# DAC_Shield_Rev_A.net
KiCad netlist of a schematic drawn in EAGLE
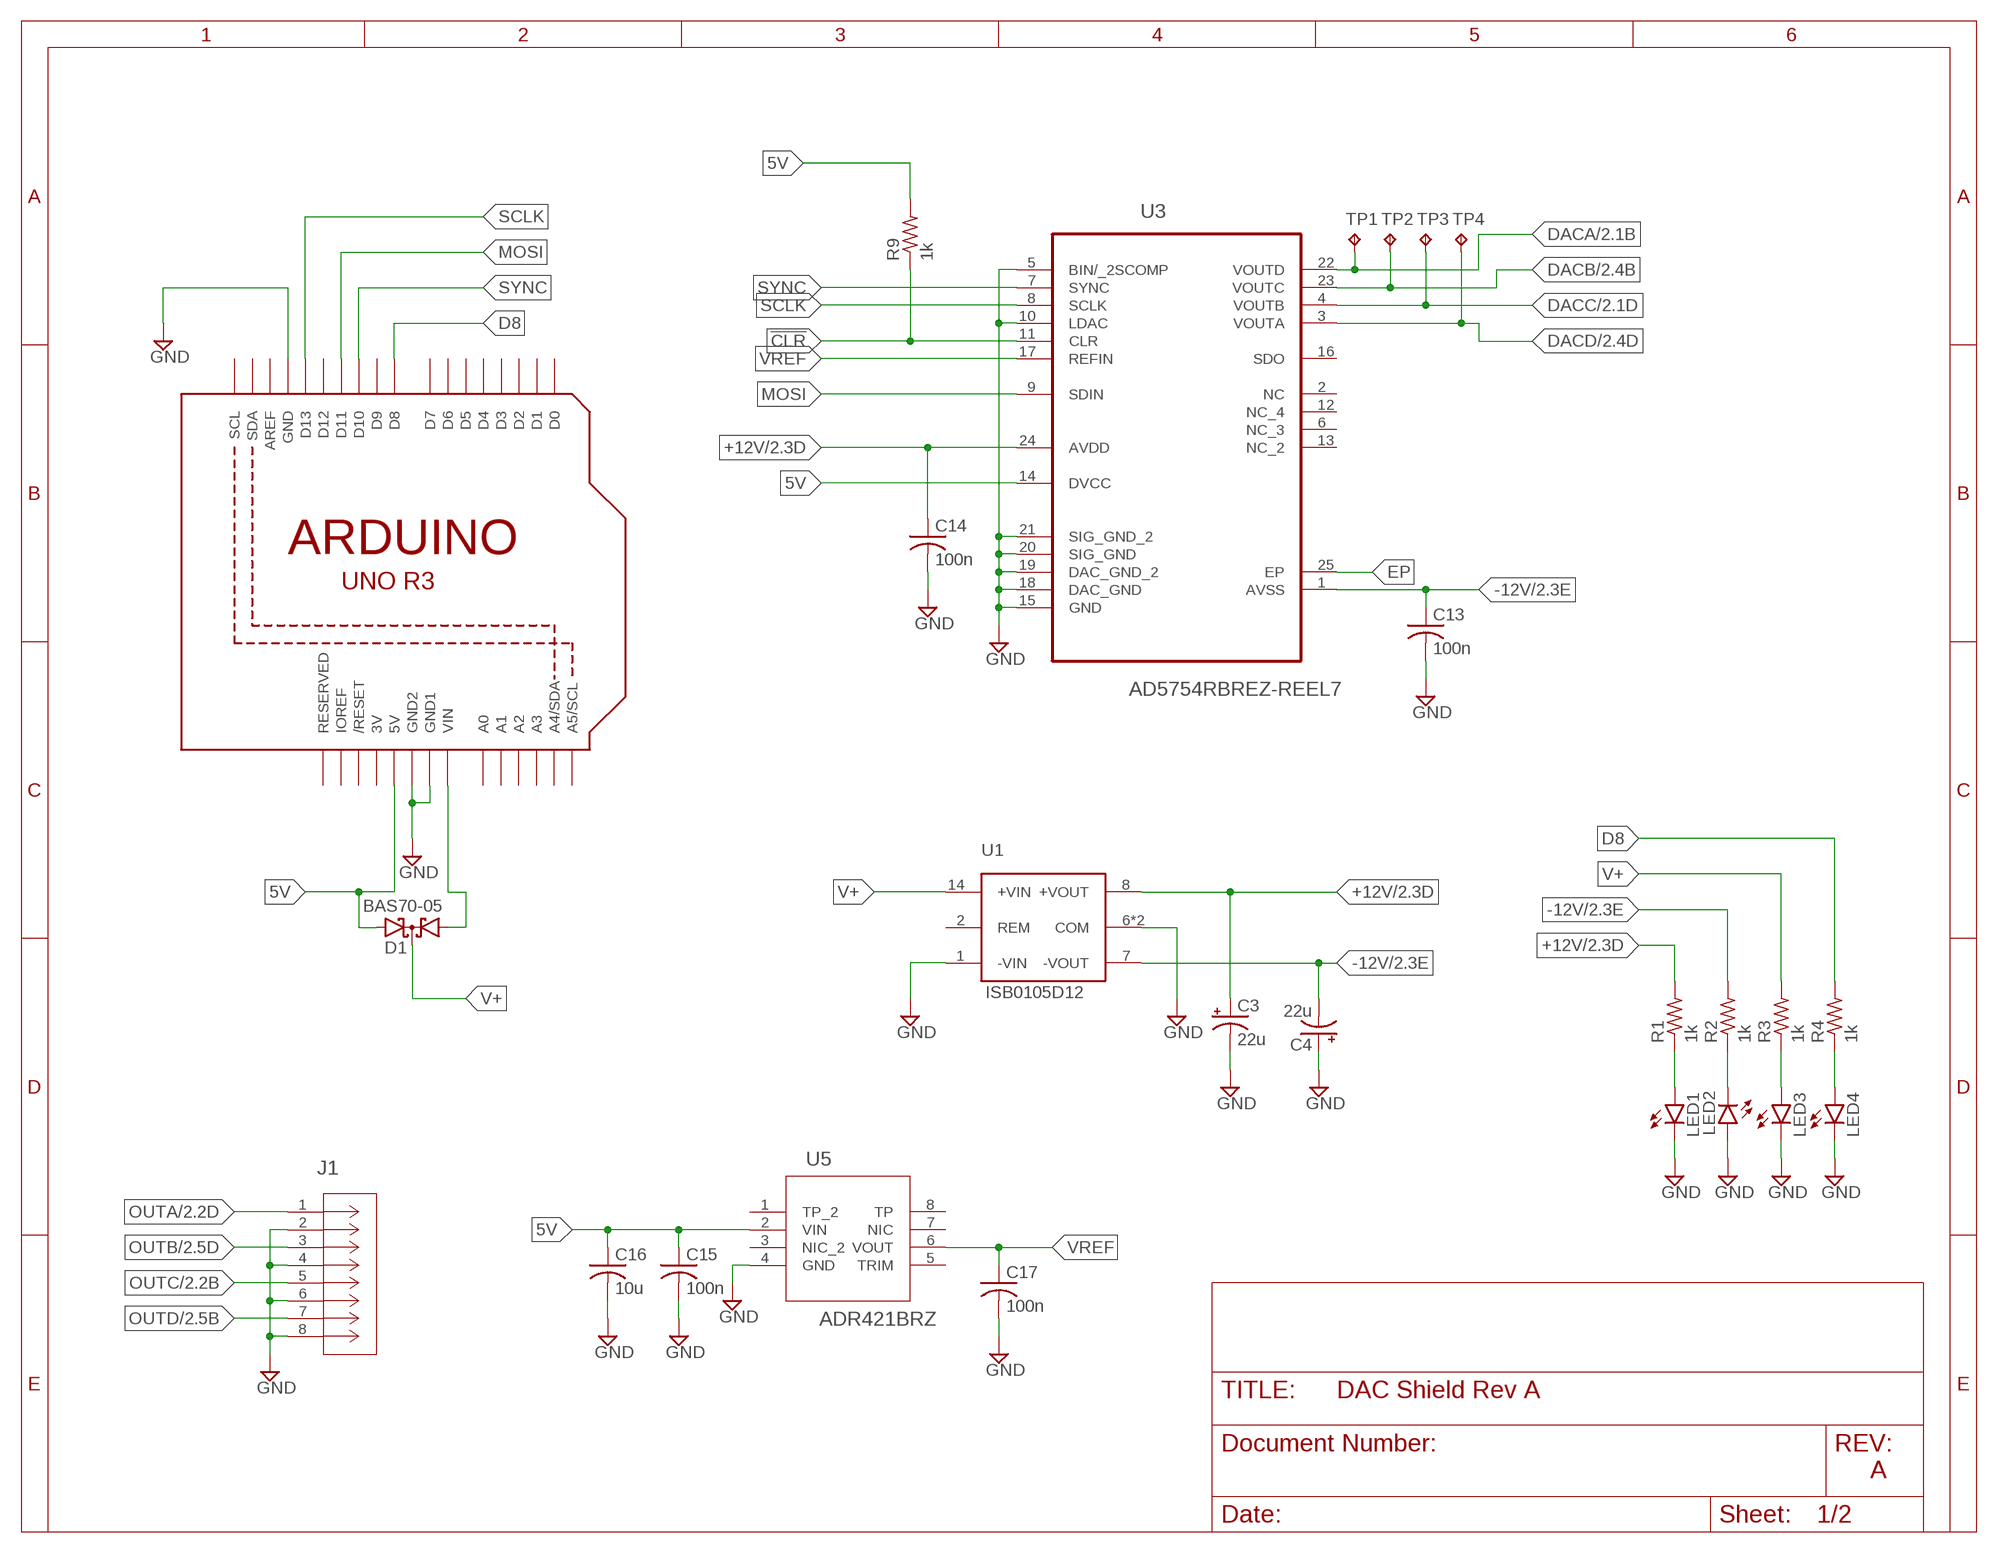
[diagram p0: schematic, sheet 1]
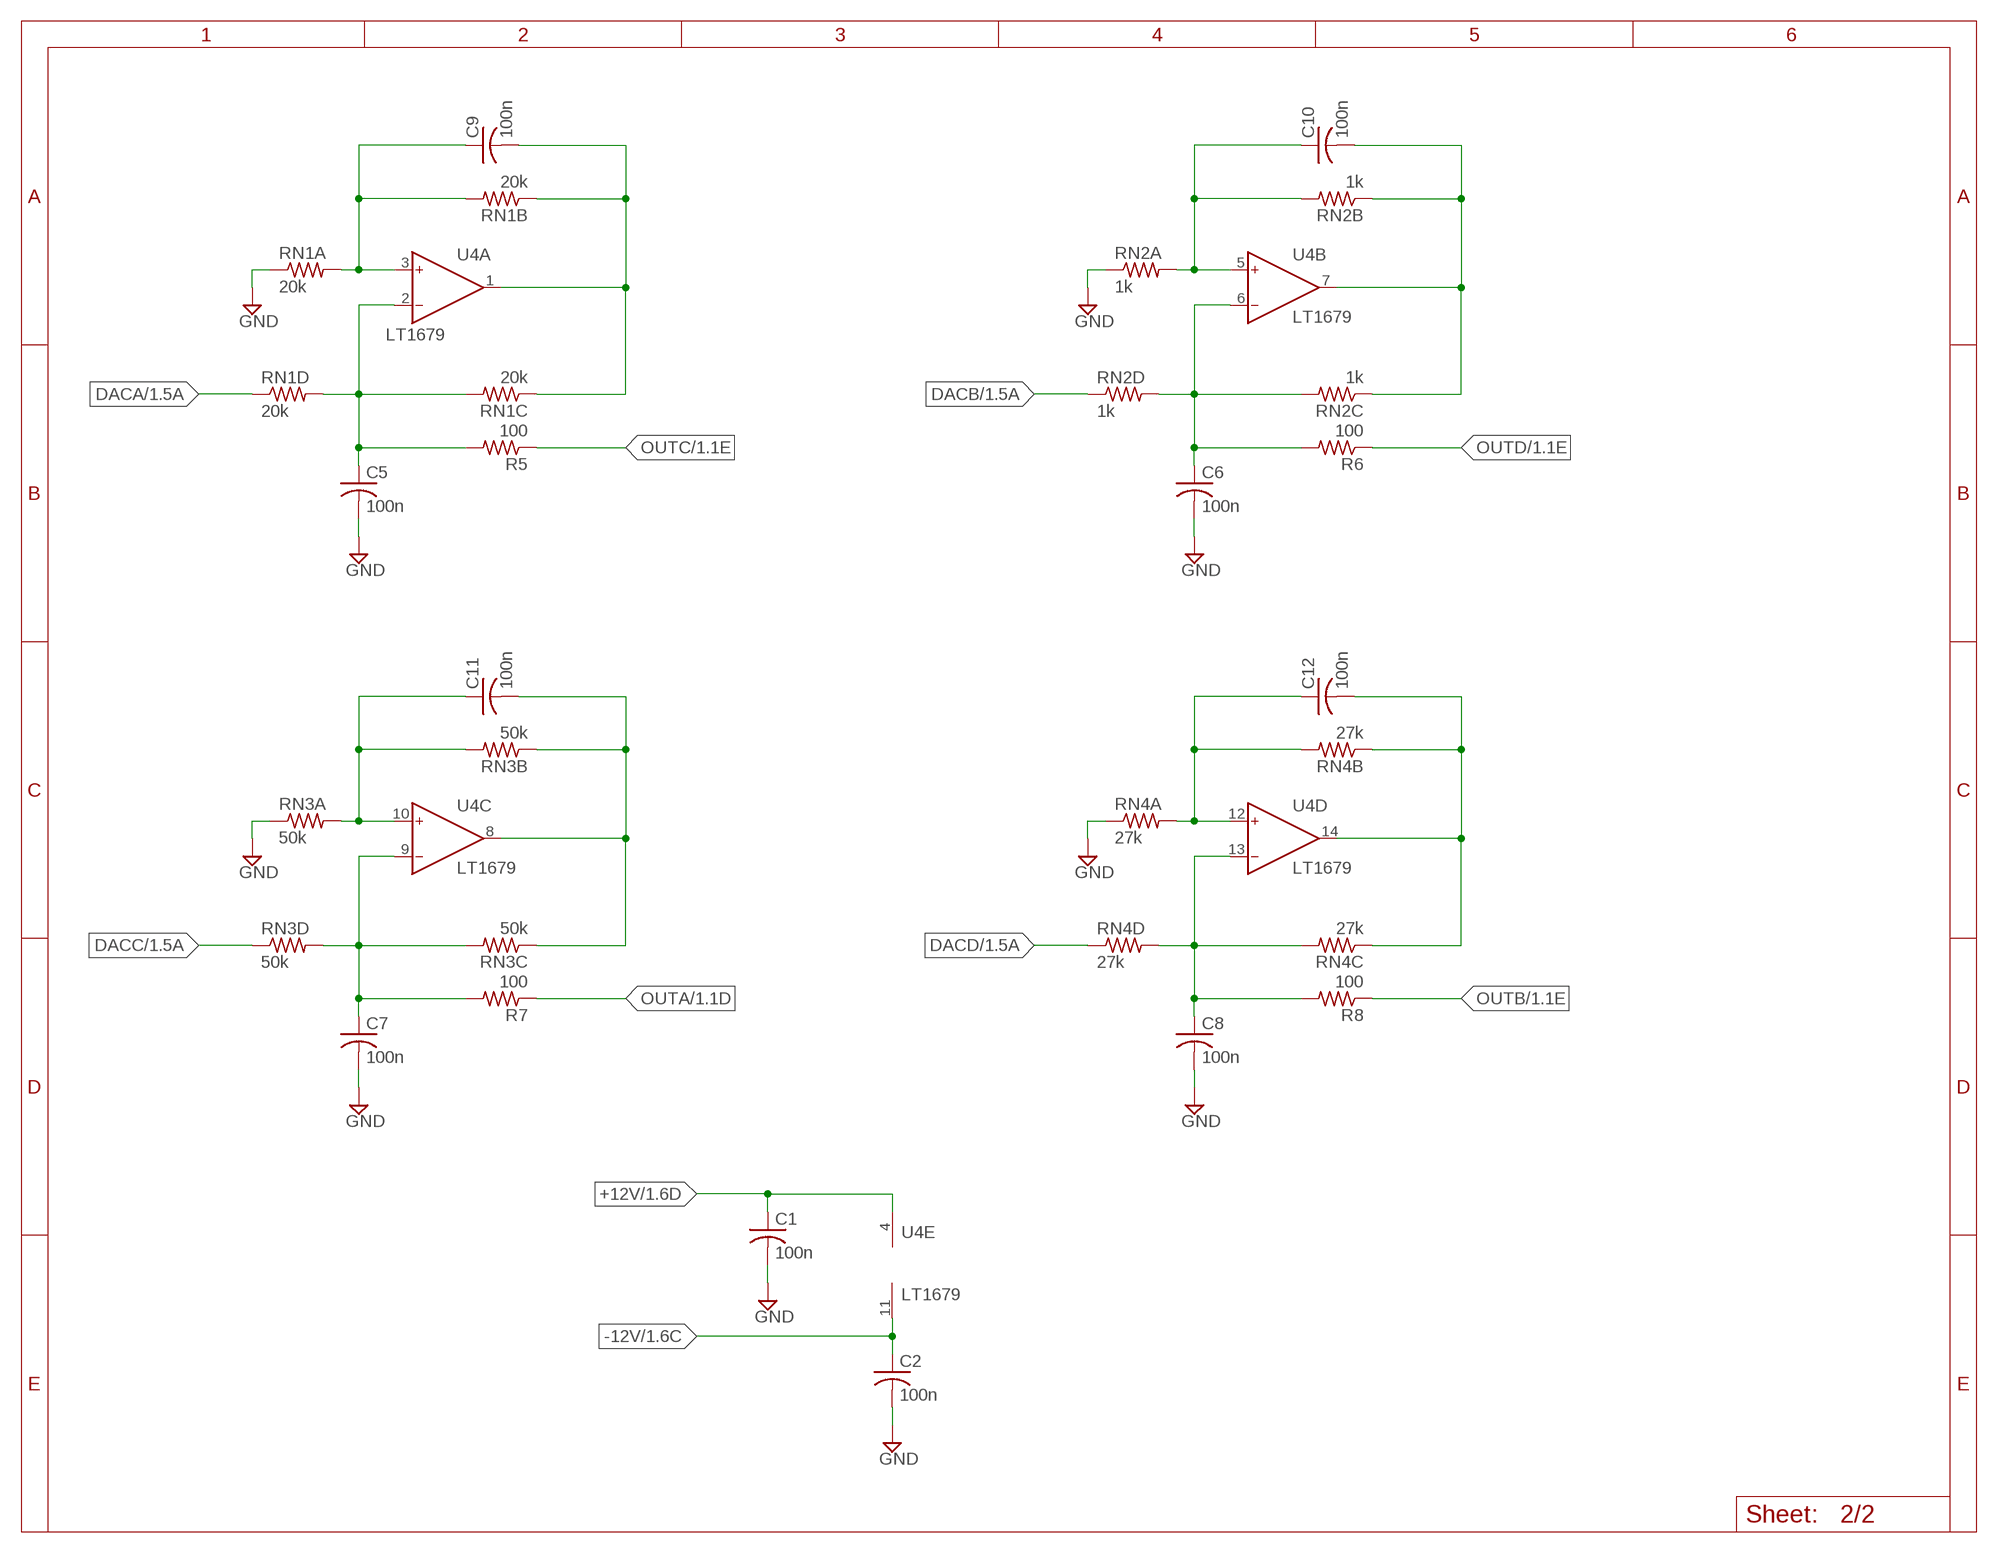
[diagram p1: schematic, sheet 2]

(export (version "E")
  (design (tool "Eeschema 10.0.6"))
  (components
    (comp (ref "C3")
      (value "22u")
      (footprint "eagle-import:C_6032-28W")
      (libsource (lib "eagle-import") (part "CPOL-USC/6032-28W"))
    )
    (comp (ref "C4")
      (value "22u")
      (footprint "eagle-import:C_6032-28W")
      (libsource (lib "eagle-import") (part "CPOL-USC/6032-28W"))
    )
    (comp (ref "C13")
      (value "100n")
      (footprint "eagle-import:C0805")
      (libsource (lib "eagle-import") (part "C-USC0805"))
    )
    (comp (ref "C14")
      (value "100n")
      (footprint "eagle-import:C0805")
      (libsource (lib "eagle-import") (part "C-USC0805"))
    )
    (comp (ref "C15")
      (value "100n")
      (footprint "eagle-import:C0805")
      (libsource (lib "eagle-import") (part "C-USC0805"))
    )
    (comp (ref "C16")
      (value "10u")
      (footprint "eagle-import:C0805")
      (libsource (lib "eagle-import") (part "C-USC0805"))
    )
    (comp (ref "C17")
      (value "100n")
      (footprint "eagle-import:C0805")
      (libsource (lib "eagle-import") (part "C-USC0805"))
    )
    (comp (ref "D1")
      (value "BAS70-05")
      (footprint "eagle-import:SOT23")
      (libsource (lib "eagle-import") (part "BAS70-05"))
    )
    (comp (ref "J1")
      (value "OSTVN08A150")
      (footprint "eagle-import:CONN_OSTVN08A150_OST")
      (fields (field (name "COPYRIGHT") "Copyright (C) 2023 Ultra Librarian. All rights reserved."))
      (libsource (lib "eagle-import") (part "OSTVN08A150"))
    )
    (comp (ref "LED1")
      (value "LEDCHIPLED_0805")
      (footprint "eagle-import:CHIPLED_0805")
      (libsource (lib "eagle-import") (part "LEDCHIPLED_0805"))
    )
    (comp (ref "LED2")
      (value "LEDCHIPLED_0805")
      (footprint "eagle-import:CHIPLED_0805")
      (libsource (lib "eagle-import") (part "LEDCHIPLED_0805"))
    )
    (comp (ref "LED3")
      (value "LEDCHIPLED_0805")
      (footprint "eagle-import:CHIPLED_0805")
      (libsource (lib "eagle-import") (part "LEDCHIPLED_0805"))
    )
    (comp (ref "LED4")
      (value "LEDCHIPLED_0805")
      (footprint "eagle-import:CHIPLED_0805")
      (libsource (lib "eagle-import") (part "LEDCHIPLED_0805"))
    )
    (comp (ref "R1")
      (value "1k")
      (footprint "eagle-import:R0805")
      (libsource (lib "eagle-import") (part "R-US_R0805"))
    )
    (comp (ref "R2")
      (value "1k")
      (footprint "eagle-import:R0805")
      (libsource (lib "eagle-import") (part "R-US_R0805"))
    )
    (comp (ref "R3")
      (value "1k")
      (footprint "eagle-import:R0805")
      (libsource (lib "eagle-import") (part "R-US_R0805"))
    )
    (comp (ref "R4")
      (value "1k")
      (footprint "eagle-import:R0805")
      (libsource (lib "eagle-import") (part "R-US_R0805"))
    )
    (comp (ref "R9")
      (value "1k")
      (footprint "eagle-import:R0805")
      (libsource (lib "eagle-import") (part "R-US_R0805"))
    )
    (comp (ref "TP1")
      (value "TPB1,27")
      (footprint "eagle-import:B1,27")
      (libsource (lib "eagle-import") (part "TPB1,27"))
    )
    (comp (ref "TP2")
      (value "TPB1,27")
      (footprint "eagle-import:B1,27")
      (libsource (lib "eagle-import") (part "TPB1,27"))
    )
    (comp (ref "TP3")
      (value "TPB1,27")
      (footprint "eagle-import:B1,27")
      (libsource (lib "eagle-import") (part "TPB1,27"))
    )
    (comp (ref "TP4")
      (value "TPB1,27")
      (footprint "eagle-import:B1,27")
      (libsource (lib "eagle-import") (part "TPB1,27"))
    )
    (comp (ref "U1")
      (value "ISB0105D12")
      (footprint "eagle-import:SOP254P1860X845-14L")
      (libsource (lib "eagle-import") (part "ISB0105D12ISB0105D12"))
    )
    (comp (ref "U2")
      (value "ARDUINOR3-BPLACE")
      (footprint "eagle-import:ARDUINOR3-BPLACE")
      (libsource (lib "eagle-import") (part "ARDUINOR3-BPLACE"))
    )
    (comp (ref "U3")
      (value "AD5754RBREZ-REEL7")
      (footprint "eagle-import:SOP65P640X120-25N")
      (libsource (lib "eagle-import") (part "AD5754RBREZ-REEL7"))
    )
    (comp (ref "U5")
      (value "ADR421BRZ")
      (footprint "eagle-import:R_8_ADI")
      (fields (field (name "COPYRIGHT") "Copyright (C) 2023 Ultra Librarian. All rights reserved."))
      (libsource (lib "eagle-import") (part "ADR421BRZ"))
    )
    (comp (ref "C1")
      (value "100n")
      (footprint "eagle-import:C0805")
      (libsource (lib "eagle-import") (part "C-USC0805"))
    )
    (comp (ref "C2")
      (value "100n")
      (footprint "eagle-import:C0805")
      (libsource (lib "eagle-import") (part "C-USC0805"))
    )
    (comp (ref "C5")
      (value "100n")
      (footprint "eagle-import:C0805")
      (libsource (lib "eagle-import") (part "C-USC0805"))
    )
    (comp (ref "C6")
      (value "100n")
      (footprint "eagle-import:C0805")
      (libsource (lib "eagle-import") (part "C-USC0805"))
    )
    (comp (ref "C7")
      (value "100n")
      (footprint "eagle-import:C0805")
      (libsource (lib "eagle-import") (part "C-USC0805"))
    )
    (comp (ref "C8")
      (value "100n")
      (footprint "eagle-import:C0805")
      (libsource (lib "eagle-import") (part "C-USC0805"))
    )
    (comp (ref "C9")
      (value "100n")
      (footprint "eagle-import:C0805")
      (libsource (lib "eagle-import") (part "C-USC0805"))
    )
    (comp (ref "C10")
      (value "100n")
      (footprint "eagle-import:C0805")
      (libsource (lib "eagle-import") (part "C-USC0805"))
    )
    (comp (ref "C11")
      (value "100n")
      (footprint "eagle-import:C0805")
      (libsource (lib "eagle-import") (part "C-USC0805"))
    )
    (comp (ref "C12")
      (value "100n")
      (footprint "eagle-import:C0805")
      (libsource (lib "eagle-import") (part "C-USC0805"))
    )
    (comp (ref "R5")
      (value "100")
      (footprint "eagle-import:R0805")
      (libsource (lib "eagle-import") (part "R-US_R0805"))
    )
    (comp (ref "R6")
      (value "100")
      (footprint "eagle-import:R0805")
      (libsource (lib "eagle-import") (part "R-US_R0805"))
    )
    (comp (ref "R7")
      (value "100")
      (footprint "eagle-import:R0805")
      (libsource (lib "eagle-import") (part "R-US_R0805"))
    )
    (comp (ref "R8")
      (value "100")
      (footprint "eagle-import:R0805")
      (libsource (lib "eagle-import") (part "R-US_R0805"))
    )
    (comp (ref "RN1")
      (value "20k")
      (footprint "eagle-import:RESCAV80P320X150X55-8N")
      (libsource (lib "eagle-import") (part "ACASA5001U5001P1ATACASA5001U5001P1AT"))
    )
    (comp (ref "RN2")
      (value "1k")
      (footprint "eagle-import:RESCAV80P320X150X55-8N")
      (libsource (lib "eagle-import") (part "ACASA5001U5001P1ATACASA5001U5001P1AT"))
    )
    (comp (ref "RN3")
      (value "50k")
      (footprint "eagle-import:RESCAV80P320X150X55-8N")
      (libsource (lib "eagle-import") (part "ACASA5001U5001P1ATACASA5001U5001P1AT"))
    )
    (comp (ref "RN4")
      (value "27k")
      (footprint "eagle-import:RESCAV80P320X150X55-8N")
      (libsource (lib "eagle-import") (part "ACASA5001U5001P1ATACASA5001U5001P1AT"))
    )
    (comp (ref "U4")
      (value "LT1679")
      (footprint "eagle-import:R_14_ADI-M")
      (fields
        (field (name "MANUFACTURER_PART_NUMBER") "AD8648ARZ")
        (field (name "COPYRIGHT") "Copyright (C) 2023 Ultra Librarian. All rights reserved.")
      )
      (libsource (lib "eagle-import") (part "AD8648ARZR_14_ADI-M"))
    )
  )
  (nets
    (net (code "1") (name "+12V") (class "Default")
      (node (ref "C1") (pin "1") (pinfunction "1_1") (pintype "passive"))
      (node (ref "C14") (pin "1") (pinfunction "1_1") (pintype "passive"))
      (node (ref "C3") (pin "+") (pinfunction "+_+") (pintype "passive"))
      (node (ref "R1") (pin "2") (pinfunction "2_2") (pintype "passive"))
      (node (ref "U1") (pin "8") (pinfunction "+VOUT_8") (pintype "bidirectional"))
      (node (ref "U3") (pin "24") (pinfunction "AVDD_24") (pintype "power_in"))
      (node (ref "U4") (pin "4") (pinfunction "V+_4") (pintype "power_in"))
    )
    (net (code "2") (name "-12V") (class "Default")
      (node (ref "C13") (pin "1") (pinfunction "1_1") (pintype "passive"))
      (node (ref "C2") (pin "1") (pinfunction "1_1") (pintype "passive"))
      (node (ref "C4") (pin "-") (pinfunction "-_-") (pintype "passive"))
      (node (ref "R2") (pin "2") (pinfunction "2_2") (pintype "passive"))
      (node (ref "U1") (pin "7") (pinfunction "-VOUT_7") (pintype "bidirectional"))
      (node (ref "U3") (pin "1") (pinfunction "AVSS_1") (pintype "passive"))
      (node (ref "U4") (pin "11") (pinfunction "V-_11") (pintype "power_in"))
    )
    (net (code "3") (name "3V") (class "Default")
      (node (ref "U2") (pin "3V") (pinfunction "3V_3V") (pintype "power_in"))
    )
    (net (code "4") (name "5V") (class "Default")
      (node (ref "C15") (pin "1") (pinfunction "1_1") (pintype "passive"))
      (node (ref "C16") (pin "1") (pinfunction "1_1") (pintype "passive"))
      (node (ref "D1") (pin "2") (pinfunction "A2_2") (pintype "passive"))
      (node (ref "R9") (pin "2") (pinfunction "2_2") (pintype "passive"))
      (node (ref "U2") (pin "5V") (pinfunction "5V_5V") (pintype "power_in"))
      (node (ref "U3") (pin "14") (pinfunction "DVCC_14") (pintype "power_in"))
      (node (ref "U5") (pin "2") (pinfunction "VIN_2") (pintype "passive"))
    )
    (net (code "5") (name "D8") (class "Default")
      (node (ref "R4") (pin "2") (pinfunction "2_2") (pintype "passive"))
      (node (ref "U2") (pin "D8") (pinfunction "D8_D8") (pintype "bidirectional"))
    )
    (net (code "6") (name "DACA") (class "Default")
      (node (ref "RN1") (pin "4") (pinfunction "1_4") (pintype "passive"))
      (node (ref "TP1") (pin "TP") (pinfunction "TP_TP") (pintype "input"))
      (node (ref "U3") (pin "22") (pinfunction "VOUTD_22") (pintype "passive"))
    )
    (net (code "7") (name "DACB") (class "Default")
      (node (ref "RN2") (pin "4") (pinfunction "1_4") (pintype "passive"))
      (node (ref "TP2") (pin "TP") (pinfunction "TP_TP") (pintype "input"))
      (node (ref "U3") (pin "23") (pinfunction "VOUTC_23") (pintype "passive"))
    )
    (net (code "8") (name "DACC") (class "Default")
      (node (ref "RN3") (pin "4") (pinfunction "1_4") (pintype "passive"))
      (node (ref "TP3") (pin "TP") (pinfunction "TP_TP") (pintype "input"))
      (node (ref "U3") (pin "4") (pinfunction "VOUTB_4") (pintype "passive"))
    )
    (net (code "9") (name "DACD") (class "Default")
      (node (ref "RN4") (pin "4") (pinfunction "1_4") (pintype "passive"))
      (node (ref "TP4") (pin "TP") (pinfunction "TP_TP") (pintype "input"))
      (node (ref "U3") (pin "3") (pinfunction "VOUTA_3") (pintype "passive"))
    )
    (net (code "10") (name "EP") (class "Default")
      (node (ref "U3") (pin "25") (pinfunction "EP_25") (pintype "power_in"))
    )
    (net (code "11") (name "GND") (class "Default")
      (node (ref "C1") (pin "2") (pinfunction "2_2") (pintype "passive"))
      (node (ref "C13") (pin "2") (pinfunction "2_2") (pintype "passive"))
      (node (ref "C14") (pin "2") (pinfunction "2_2") (pintype "passive"))
      (node (ref "C15") (pin "2") (pinfunction "2_2") (pintype "passive"))
      (node (ref "C16") (pin "2") (pinfunction "2_2") (pintype "passive"))
      (node (ref "C17") (pin "2") (pinfunction "2_2") (pintype "passive"))
      (node (ref "C2") (pin "2") (pinfunction "2_2") (pintype "passive"))
      (node (ref "C3") (pin "-") (pinfunction "-_-") (pintype "passive"))
      (node (ref "C4") (pin "+") (pinfunction "+_+") (pintype "passive"))
      (node (ref "C5") (pin "2") (pinfunction "2_2") (pintype "passive"))
      (node (ref "C6") (pin "2") (pinfunction "2_2") (pintype "passive"))
      (node (ref "C7") (pin "2") (pinfunction "2_2") (pintype "passive"))
      (node (ref "C8") (pin "2") (pinfunction "2_2") (pintype "passive"))
      (node (ref "J1") (pin "2") (pinfunction "2_2") (pintype "passive"))
      (node (ref "J1") (pin "4") (pinfunction "4_4") (pintype "passive"))
      (node (ref "J1") (pin "6") (pinfunction "6_6") (pintype "passive"))
      (node (ref "J1") (pin "8") (pinfunction "8_8") (pintype "passive"))
      (node (ref "LED1") (pin "C") (pinfunction "C_C") (pintype "passive"))
      (node (ref "LED2") (pin "A") (pinfunction "A_A") (pintype "passive"))
      (node (ref "LED3") (pin "C") (pinfunction "C_C") (pintype "passive"))
      (node (ref "LED4") (pin "C") (pinfunction "C_C") (pintype "passive"))
      (node (ref "RN1") (pin "1") (pinfunction "1_1") (pintype "passive"))
      (node (ref "RN2") (pin "1") (pinfunction "1_1") (pintype "passive"))
      (node (ref "RN3") (pin "1") (pinfunction "1_1") (pintype "passive"))
      (node (ref "RN4") (pin "1") (pinfunction "1_1") (pintype "passive"))
      (node (ref "U1") (pin "1") (pinfunction "-VIN_1") (pintype "bidirectional"))
      (node (ref "U1") (pin "6") (pinfunction "COM_6") (pintype "bidirectional"))
      (node (ref "U1") (pin "9") (pinfunction "COM_9") (pintype "bidirectional"))
      (node (ref "U2") (pin "GND") (pinfunction "GND_GND") (pintype "power_in"))
      (node (ref "U2") (pin "GND1") (pinfunction "GND1_GND1") (pintype "power_in"))
      (node (ref "U2") (pin "GND2") (pinfunction "GND2_GND2") (pintype "power_in"))
      (node (ref "U3") (pin "10") (pinfunction "LDAC_10") (pintype "passive"))
      (node (ref "U3") (pin "15") (pinfunction "GND_15") (pintype "passive"))
      (node (ref "U3") (pin "18") (pinfunction "DAC_GND_18") (pintype "passive"))
      (node (ref "U3") (pin "19") (pinfunction "DAC_GND_2_19") (pintype "passive"))
      (node (ref "U3") (pin "20") (pinfunction "SIG_GND_20") (pintype "passive"))
      (node (ref "U3") (pin "21") (pinfunction "SIG_GND_2_21") (pintype "passive"))
      (node (ref "U3") (pin "5") (pinfunction "BIN/_2SCOMP_5") (pintype "passive"))
      (node (ref "U5") (pin "4") (pinfunction "GND_4") (pintype "passive"))
    )
    (net (code "12") (name "MOSI") (class "Default")
      (node (ref "U2") (pin "D11") (pinfunction "D11_D11") (pintype "bidirectional"))
      (node (ref "U3") (pin "9") (pinfunction "SDIN_9") (pintype "passive"))
    )
    (net (code "13") (name "Net-(D1-A1)") (class "Default")
      (node (ref "D1") (pin "1") (pinfunction "A1_1") (pintype "passive"))
      (node (ref "U2") (pin "VIN") (pinfunction "VIN_VIN") (pintype "power_in"))
    )
    (net (code "14") (name "Net-(LED1-PadA)") (class "Default")
      (node (ref "LED1") (pin "A") (pinfunction "A_A") (pintype "passive"))
      (node (ref "R1") (pin "1") (pinfunction "1_1") (pintype "passive"))
    )
    (net (code "15") (name "Net-(LED2-PadC)") (class "Default")
      (node (ref "LED2") (pin "C") (pinfunction "C_C") (pintype "passive"))
      (node (ref "R2") (pin "1") (pinfunction "1_1") (pintype "passive"))
    )
    (net (code "16") (name "Net-(LED3-PadA)") (class "Default")
      (node (ref "LED3") (pin "A") (pinfunction "A_A") (pintype "passive"))
      (node (ref "R3") (pin "1") (pinfunction "1_1") (pintype "passive"))
    )
    (net (code "17") (name "Net-(LED4-PadA)") (class "Default")
      (node (ref "LED4") (pin "A") (pinfunction "A_A") (pintype "passive"))
      (node (ref "R4") (pin "1") (pinfunction "1_1") (pintype "passive"))
    )
    (net (code "18") (name "Net-(RN1A-2)") (class "Default")
      (node (ref "C9") (pin "1") (pinfunction "1_1") (pintype "passive"))
      (node (ref "RN1") (pin "7") (pinfunction "2_7") (pintype "passive"))
      (node (ref "RN1") (pin "8") (pinfunction "2_8") (pintype "passive"))
      (node (ref "U4") (pin "3") (pinfunction "IN+_3") (pintype "input"))
    )
    (net (code "19") (name "Net-(RN1B-1)") (class "Default")
      (node (ref "C9") (pin "2") (pinfunction "2_2") (pintype "passive"))
      (node (ref "RN1") (pin "2") (pinfunction "1_2") (pintype "passive"))
      (node (ref "RN1") (pin "3") (pinfunction "1_3") (pintype "passive"))
      (node (ref "U4") (pin "1") (pinfunction "OUT_1") (pintype "output"))
    )
    (net (code "20") (name "Net-(RN1C-2)") (class "Default")
      (node (ref "C5") (pin "1") (pinfunction "1_1") (pintype "passive"))
      (node (ref "R5") (pin "2") (pinfunction "2_2") (pintype "passive"))
      (node (ref "RN1") (pin "5") (pinfunction "2_5") (pintype "passive"))
      (node (ref "RN1") (pin "6") (pinfunction "2_6") (pintype "passive"))
      (node (ref "U4") (pin "2") (pinfunction "IN-_2") (pintype "input"))
    )
    (net (code "21") (name "Net-(RN2A-2)") (class "Default")
      (node (ref "C10") (pin "1") (pinfunction "1_1") (pintype "passive"))
      (node (ref "RN2") (pin "7") (pinfunction "2_7") (pintype "passive"))
      (node (ref "RN2") (pin "8") (pinfunction "2_8") (pintype "passive"))
      (node (ref "U4") (pin "5") (pinfunction "IN+_5") (pintype "input"))
    )
    (net (code "22") (name "Net-(RN2B-1)") (class "Default")
      (node (ref "C10") (pin "2") (pinfunction "2_2") (pintype "passive"))
      (node (ref "RN2") (pin "2") (pinfunction "1_2") (pintype "passive"))
      (node (ref "RN2") (pin "3") (pinfunction "1_3") (pintype "passive"))
      (node (ref "U4") (pin "7") (pinfunction "OUT_7") (pintype "output"))
    )
    (net (code "23") (name "Net-(RN2C-2)") (class "Default")
      (node (ref "C6") (pin "1") (pinfunction "1_1") (pintype "passive"))
      (node (ref "R6") (pin "2") (pinfunction "2_2") (pintype "passive"))
      (node (ref "RN2") (pin "5") (pinfunction "2_5") (pintype "passive"))
      (node (ref "RN2") (pin "6") (pinfunction "2_6") (pintype "passive"))
      (node (ref "U4") (pin "6") (pinfunction "IN-_6") (pintype "input"))
    )
    (net (code "24") (name "Net-(RN3A-2)") (class "Default")
      (node (ref "C11") (pin "1") (pinfunction "1_1") (pintype "passive"))
      (node (ref "RN3") (pin "7") (pinfunction "2_7") (pintype "passive"))
      (node (ref "RN3") (pin "8") (pinfunction "2_8") (pintype "passive"))
      (node (ref "U4") (pin "10") (pinfunction "IN+_10") (pintype "input"))
    )
    (net (code "25") (name "Net-(RN3B-1)") (class "Default")
      (node (ref "C11") (pin "2") (pinfunction "2_2") (pintype "passive"))
      (node (ref "RN3") (pin "2") (pinfunction "1_2") (pintype "passive"))
      (node (ref "RN3") (pin "3") (pinfunction "1_3") (pintype "passive"))
      (node (ref "U4") (pin "8") (pinfunction "OUT_8") (pintype "output"))
    )
    (net (code "26") (name "Net-(RN3C-2)") (class "Default")
      (node (ref "C7") (pin "1") (pinfunction "1_1") (pintype "passive"))
      (node (ref "R7") (pin "2") (pinfunction "2_2") (pintype "passive"))
      (node (ref "RN3") (pin "5") (pinfunction "2_5") (pintype "passive"))
      (node (ref "RN3") (pin "6") (pinfunction "2_6") (pintype "passive"))
      (node (ref "U4") (pin "9") (pinfunction "IN-_9") (pintype "input"))
    )
    (net (code "27") (name "Net-(RN4A-2)") (class "Default")
      (node (ref "C12") (pin "1") (pinfunction "1_1") (pintype "passive"))
      (node (ref "RN4") (pin "7") (pinfunction "2_7") (pintype "passive"))
      (node (ref "RN4") (pin "8") (pinfunction "2_8") (pintype "passive"))
      (node (ref "U4") (pin "12") (pinfunction "IN+_12") (pintype "input"))
    )
    (net (code "28") (name "Net-(RN4B-1)") (class "Default")
      (node (ref "C12") (pin "2") (pinfunction "2_2") (pintype "passive"))
      (node (ref "RN4") (pin "2") (pinfunction "1_2") (pintype "passive"))
      (node (ref "RN4") (pin "3") (pinfunction "1_3") (pintype "passive"))
      (node (ref "U4") (pin "14") (pinfunction "OUT_14") (pintype "output"))
    )
    (net (code "29") (name "Net-(RN4C-2)") (class "Default")
      (node (ref "C8") (pin "1") (pinfunction "1_1") (pintype "passive"))
      (node (ref "R8") (pin "2") (pinfunction "2_2") (pintype "passive"))
      (node (ref "RN4") (pin "5") (pinfunction "2_5") (pintype "passive"))
      (node (ref "RN4") (pin "6") (pinfunction "2_6") (pintype "passive"))
      (node (ref "U4") (pin "13") (pinfunction "IN-_13") (pintype "input"))
    )
    (net (code "30") (name "OUTA") (class "Default")
      (node (ref "J1") (pin "1") (pinfunction "1_1") (pintype "passive"))
      (node (ref "R7") (pin "1") (pinfunction "1_1") (pintype "passive"))
    )
    (net (code "31") (name "OUTB") (class "Default")
      (node (ref "J1") (pin "3") (pinfunction "3_3") (pintype "passive"))
      (node (ref "R8") (pin "1") (pinfunction "1_1") (pintype "passive"))
    )
    (net (code "32") (name "OUTC") (class "Default")
      (node (ref "J1") (pin "5") (pinfunction "5_5") (pintype "passive"))
      (node (ref "R5") (pin "1") (pinfunction "1_1") (pintype "passive"))
    )
    (net (code "33") (name "OUTD") (class "Default")
      (node (ref "J1") (pin "7") (pinfunction "7_7") (pintype "passive"))
      (node (ref "R6") (pin "1") (pinfunction "1_1") (pintype "passive"))
    )
    (net (code "34") (name "SCLK") (class "Default")
      (node (ref "U2") (pin "D13") (pinfunction "D13_D13") (pintype "bidirectional"))
      (node (ref "U3") (pin "8") (pinfunction "SCLK_8") (pintype "passive"))
    )
    (net (code "35") (name "SYNC") (class "Default")
      (node (ref "U2") (pin "D10") (pinfunction "D10_D10") (pintype "bidirectional"))
      (node (ref "U3") (pin "7") (pinfunction "SYNC_7") (pintype "passive"))
    )
    (net (code "36") (name "V+") (class "Default")
      (node (ref "D1") (pin "3") (pinfunction "C_3") (pintype "passive"))
      (node (ref "R3") (pin "2") (pinfunction "2_2") (pintype "passive"))
      (node (ref "U1") (pin "14") (pinfunction "+VIN_14") (pintype "bidirectional"))
    )
    (net (code "37") (name "VREF") (class "Default")
      (node (ref "C17") (pin "1") (pinfunction "1_1") (pintype "passive"))
      (node (ref "U3") (pin "17") (pinfunction "REFIN_17") (pintype "passive"))
      (node (ref "U5") (pin "6") (pinfunction "VOUT_6") (pintype "passive"))
    )
    (net (code "38") (name "unconnected-(U1-REM-Pad2)") (class "Default")
      (node (ref "U1") (pin "2") (pinfunction "REM_2") (pintype "bidirectional"))
    )
    (net (code "39") (name "unconnected-(U2-A4{slash}SDA-PadA4)") (class "Default")
      (node (ref "U2") (pin "A4") (pinfunction "A4/SDA_A4") (pintype "bidirectional"))
    )
    (net (code "40") (name "unconnected-(U2-A5{slash}SCL-PadA5)") (class "Default")
      (node (ref "U2") (pin "A5") (pinfunction "A5/SCL_A5") (pintype "bidirectional"))
    )
    (net (code "41") (name "unconnected-(U2-PadA0)") (class "Default")
      (node (ref "U2") (pin "A0") (pinfunction "A0_A0") (pintype "bidirectional"))
    )
    (net (code "42") (name "unconnected-(U2-PadA1)") (class "Default")
      (node (ref "U2") (pin "A1") (pinfunction "A1_A1") (pintype "bidirectional"))
    )
    (net (code "43") (name "unconnected-(U2-PadA2)") (class "Default")
      (node (ref "U2") (pin "A2") (pinfunction "A2_A2") (pintype "bidirectional"))
    )
    (net (code "44") (name "unconnected-(U2-PadA3)") (class "Default")
      (node (ref "U2") (pin "A3") (pinfunction "A3_A3") (pintype "bidirectional"))
    )
    (net (code "45") (name "unconnected-(U2-PadAREF)") (class "Default")
      (node (ref "U2") (pin "AREF") (pinfunction "AREF_AREF") (pintype "bidirectional"))
    )
    (net (code "46") (name "unconnected-(U2-PadD0)") (class "Default")
      (node (ref "U2") (pin "D0") (pinfunction "D0_D0") (pintype "bidirectional"))
    )
    (net (code "47") (name "unconnected-(U2-PadD1)") (class "Default")
      (node (ref "U2") (pin "D1") (pinfunction "D1_D1") (pintype "bidirectional"))
    )
    (net (code "48") (name "unconnected-(U2-PadD2)") (class "Default")
      (node (ref "U2") (pin "D2") (pinfunction "D2_D2") (pintype "bidirectional"))
    )
    (net (code "49") (name "unconnected-(U2-PadD3)") (class "Default")
      (node (ref "U2") (pin "D3") (pinfunction "D3_D3") (pintype "bidirectional"))
    )
    (net (code "50") (name "unconnected-(U2-PadD4)") (class "Default")
      (node (ref "U2") (pin "D4") (pinfunction "D4_D4") (pintype "bidirectional"))
    )
    (net (code "51") (name "unconnected-(U2-PadD5)") (class "Default")
      (node (ref "U2") (pin "D5") (pinfunction "D5_D5") (pintype "bidirectional"))
    )
    (net (code "52") (name "unconnected-(U2-PadD6)") (class "Default")
      (node (ref "U2") (pin "D6") (pinfunction "D6_D6") (pintype "bidirectional"))
    )
    (net (code "53") (name "unconnected-(U2-PadD7)") (class "Default")
      (node (ref "U2") (pin "D7") (pinfunction "D7_D7") (pintype "bidirectional"))
    )
    (net (code "54") (name "unconnected-(U2-PadD9)") (class "Default")
      (node (ref "U2") (pin "D9") (pinfunction "D9_D9") (pintype "bidirectional"))
    )
    (net (code "55") (name "unconnected-(U2-PadD12)") (class "Default")
      (node (ref "U2") (pin "D12") (pinfunction "D12_D12") (pintype "bidirectional"))
    )
    (net (code "56") (name "unconnected-(U2-PadIOREF)") (class "Default")
      (node (ref "U2") (pin "IOREF") (pinfunction "IOREF_IOREF") (pintype "output"))
    )
    (net (code "57") (name "unconnected-(U2-PadRESERVED)") (class "Default")
      (node (ref "U2") (pin "RESERVED") (pinfunction "RESERVED_RESERVED") (pintype "no_connect"))
    )
    (net (code "58") (name "unconnected-(U2-PadSCL)") (class "Default")
      (node (ref "U2") (pin "SCL") (pinfunction "SCL_SCL") (pintype "bidirectional"))
    )
    (net (code "59") (name "unconnected-(U2-PadSDA)") (class "Default")
      (node (ref "U2") (pin "SDA") (pinfunction "SDA_SDA") (pintype "bidirectional"))
    )
    (net (code "60") (name "unconnected-(U2-{slash}RESET-PadRESET)") (class "Default")
      (node (ref "U2") (pin "RESET") (pinfunction "/RESET_RESET") (pintype "bidirectional"))
    )
    (net (code "61") (name "unconnected-(U3-NC-Pad2)") (class "Default")
      (node (ref "U3") (pin "2") (pinfunction "NC_2") (pintype "passive"))
    )
    (net (code "62") (name "unconnected-(U3-NC_2-Pad13)") (class "Default")
      (node (ref "U3") (pin "13") (pinfunction "NC_2_13") (pintype "passive"))
    )
    (net (code "63") (name "unconnected-(U3-NC_3-Pad6)") (class "Default")
      (node (ref "U3") (pin "6") (pinfunction "NC_3_6") (pintype "passive"))
    )
    (net (code "64") (name "unconnected-(U3-NC_4-Pad12)") (class "Default")
      (node (ref "U3") (pin "12") (pinfunction "NC_4_12") (pintype "passive"))
    )
    (net (code "65") (name "unconnected-(U3-SDO-Pad16)") (class "Default")
      (node (ref "U3") (pin "16") (pinfunction "SDO_16") (pintype "passive"))
    )
    (net (code "66") (name "unconnected-(U5-NIC-Pad7)") (class "Default")
      (node (ref "U5") (pin "7") (pinfunction "NIC_7") (pintype "passive"))
    )
    (net (code "67") (name "unconnected-(U5-NIC_2-Pad3)") (class "Default")
      (node (ref "U5") (pin "3") (pinfunction "NIC_2_3") (pintype "passive"))
    )
    (net (code "68") (name "unconnected-(U5-TP-Pad8)") (class "Default")
      (node (ref "U5") (pin "8") (pinfunction "TP_8") (pintype "passive"))
    )
    (net (code "69") (name "unconnected-(U5-TP_2-Pad1)") (class "Default")
      (node (ref "U5") (pin "1") (pinfunction "TP_2_1") (pintype "passive"))
    )
    (net (code "70") (name "unconnected-(U5-TRIM-Pad5)") (class "Default")
      (node (ref "U5") (pin "5") (pinfunction "TRIM_5") (pintype "passive"))
    )
    (net (code "71") (name "~{CLR}") (class "Default")
      (node (ref "R9") (pin "1") (pinfunction "1_1") (pintype "passive"))
      (node (ref "U3") (pin "11") (pinfunction "CLR_11") (pintype "passive"))
    )
  )
)
